# button.net
KiCad netlist of a schematic drawn in Altium Designer
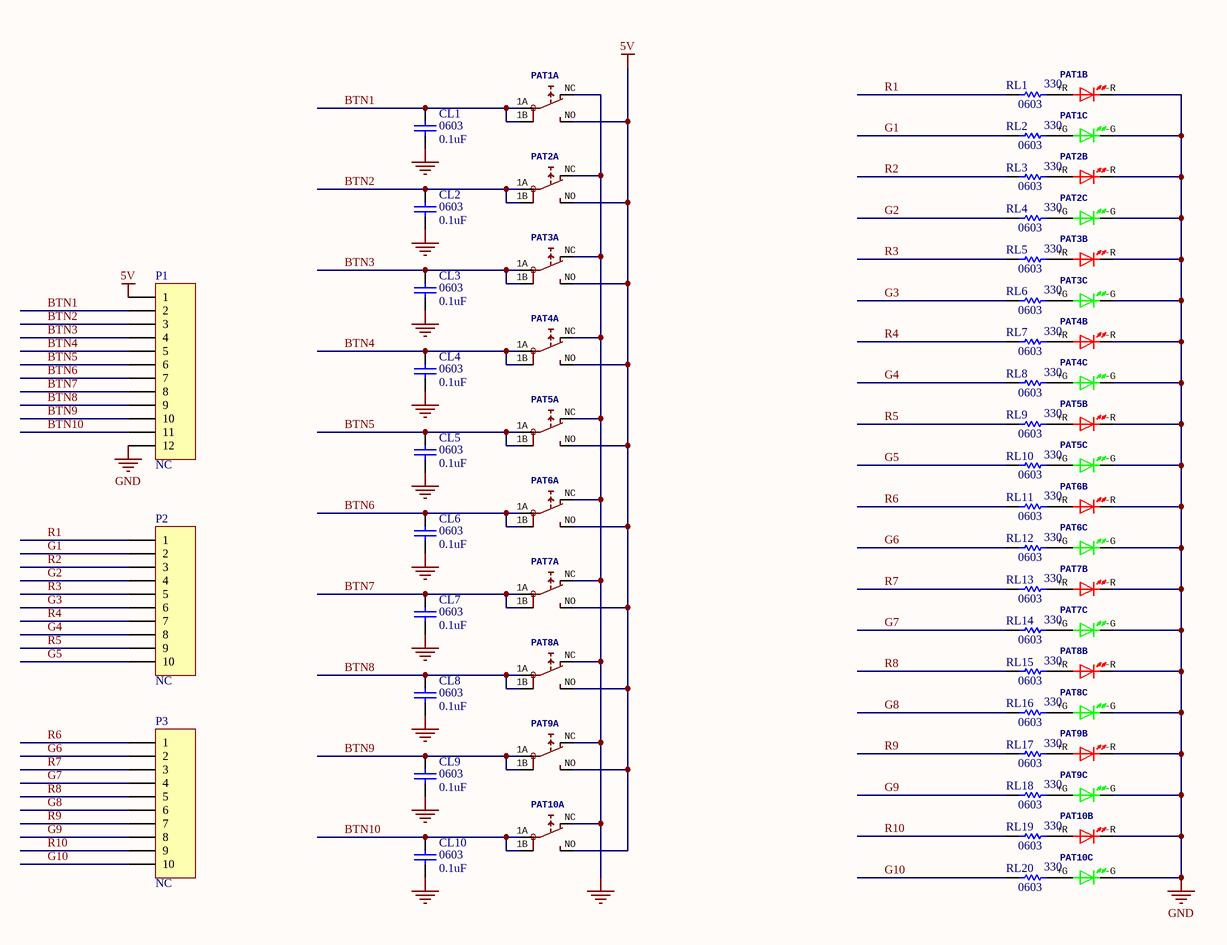
[diagram p0: button.SchDoc]

(export (version "E")
  (design (tool "Eeschema 10.0.6"))
  (components
    (comp (ref "CL1")
      (value "0603")
      (footprint "C0603")
      (description "CAP CER 0.1UF 50V X5R 0603")
      (fields (field (name "ALTIUM_VALUE") "0.1uF") (field (name "TOLERANCE") "10%"))
      (libsource (lib "Miscellaneous Devices") (part "Cap"))
    )
    (comp (ref "CL2")
      (value "0603")
      (footprint "C0603")
      (description "CAP CER 0.1UF 50V X5R 0603")
      (fields (field (name "ALTIUM_VALUE") "0.1uF") (field (name "TOLERANCE") "10%"))
      (libsource (lib "Miscellaneous Devices") (part "Cap"))
    )
    (comp (ref "CL3")
      (value "0603")
      (footprint "C0603")
      (description "CAP CER 0.1UF 50V X5R 0603")
      (fields (field (name "ALTIUM_VALUE") "0.1uF") (field (name "TOLERANCE") "10%"))
      (libsource (lib "Miscellaneous Devices") (part "Cap"))
    )
    (comp (ref "CL4")
      (value "0603")
      (footprint "C0603")
      (description "CAP CER 0.1UF 50V X5R 0603")
      (fields (field (name "ALTIUM_VALUE") "0.1uF") (field (name "TOLERANCE") "10%"))
      (libsource (lib "Miscellaneous Devices") (part "Cap"))
    )
    (comp (ref "CL5")
      (value "0603")
      (footprint "C0603")
      (description "CAP CER 0.1UF 50V X5R 0603")
      (fields (field (name "ALTIUM_VALUE") "0.1uF") (field (name "TOLERANCE") "10%"))
      (libsource (lib "Miscellaneous Devices") (part "Cap"))
    )
    (comp (ref "CL6")
      (value "0603")
      (footprint "C0603")
      (description "CAP CER 0.1UF 50V X5R 0603")
      (fields (field (name "ALTIUM_VALUE") "0.1uF") (field (name "TOLERANCE") "10%"))
      (libsource (lib "Miscellaneous Devices") (part "Cap"))
    )
    (comp (ref "CL7")
      (value "0603")
      (footprint "C0603")
      (description "CAP CER 0.1UF 50V X5R 0603")
      (fields (field (name "ALTIUM_VALUE") "0.1uF") (field (name "TOLERANCE") "10%"))
      (libsource (lib "Miscellaneous Devices") (part "Cap"))
    )
    (comp (ref "CL8")
      (value "0603")
      (footprint "C0603")
      (description "CAP CER 0.1UF 50V X5R 0603")
      (fields (field (name "ALTIUM_VALUE") "0.1uF") (field (name "TOLERANCE") "10%"))
      (libsource (lib "Miscellaneous Devices") (part "Cap"))
    )
    (comp (ref "CL9")
      (value "0603")
      (footprint "C0603")
      (description "CAP CER 0.1UF 50V X5R 0603")
      (fields (field (name "ALTIUM_VALUE") "0.1uF") (field (name "TOLERANCE") "10%"))
      (libsource (lib "Miscellaneous Devices") (part "Cap"))
    )
    (comp (ref "CL10")
      (value "0603")
      (footprint "C0603")
      (description "CAP CER 0.1UF 50V X5R 0603")
      (fields (field (name "ALTIUM_VALUE") "0.1uF") (field (name "TOLERANCE") "10%"))
      (libsource (lib "Miscellaneous Devices") (part "Cap"))
    )
    (comp (ref "P1")
      (value "NC")
      (footprint "12P HEADER")
      (description "Header, 12-Pin")
      (fields (field (name "PUBLISHER") "Altium Limited"))
      (libsource (lib "Miscellaneous Connectors") (part "Header 12"))
    )
    (comp (ref "P2")
      (value "NC")
      (footprint "10P HEADER")
      (description "Header, 10-Pin")
      (fields (field (name "PUBLISHER") "Altium Limited"))
      (libsource (lib "Miscellaneous Connectors") (part "Header 10"))
    )
    (comp (ref "P3")
      (value "NC")
      (footprint "10P HEADER")
      (description "Header, 10-Pin")
      (fields (field (name "PUBLISHER") "Altium Limited"))
      (libsource (lib "Miscellaneous Connectors") (part "Header 10"))
    )
    (comp (ref "PAT1")
      (value "55?-2LED01")
      (footprint "5501-2LED")
      (description "Pushbutton Switch SPDT Keyswitch, Illuminated Through Hole")
      (libsource (lib "Schlib") (part "5501MBLKREDGRN"))
    )
    (comp (ref "PAT2")
      (value "55?-2LED01")
      (footprint "5501-2LED")
      (description "Pushbutton Switch SPDT Keyswitch, Illuminated Through Hole")
      (libsource (lib "Schlib") (part "5501MBLKREDGRN"))
    )
    (comp (ref "PAT3")
      (value "55?-2LED01")
      (footprint "5501-2LED")
      (description "Pushbutton Switch SPDT Keyswitch, Illuminated Through Hole")
      (libsource (lib "Schlib") (part "5501MBLKREDGRN"))
    )
    (comp (ref "PAT4")
      (value "55?-2LED01")
      (footprint "5501-2LED")
      (description "Pushbutton Switch SPDT Keyswitch, Illuminated Through Hole")
      (libsource (lib "Schlib") (part "5501MBLKREDGRN"))
    )
    (comp (ref "PAT5")
      (value "55?-2LED01")
      (footprint "5501-2LED")
      (description "Pushbutton Switch SPDT Keyswitch, Illuminated Through Hole")
      (libsource (lib "Schlib") (part "5501MBLKREDGRN"))
    )
    (comp (ref "PAT6")
      (value "55?-2LED01")
      (footprint "5501-2LED")
      (description "Pushbutton Switch SPDT Keyswitch, Illuminated Through Hole")
      (libsource (lib "Schlib") (part "5501MBLKREDGRN"))
    )
    (comp (ref "PAT7")
      (value "55?-2LED01")
      (footprint "5501-2LED")
      (description "Pushbutton Switch SPDT Keyswitch, Illuminated Through Hole")
      (libsource (lib "Schlib") (part "5501MBLKREDGRN"))
    )
    (comp (ref "PAT8")
      (value "55?-2LED01")
      (footprint "5501-2LED")
      (description "Pushbutton Switch SPDT Keyswitch, Illuminated Through Hole")
      (libsource (lib "") (part "5501MBLKREDGRN_1"))
    )
    (comp (ref "PAT9")
      (value "55?-2LED01")
      (footprint "5501-2LED")
      (description "Pushbutton Switch SPDT Keyswitch, Illuminated Through Hole")
      (libsource (lib "Schlib") (part "5501MBLKREDGRN"))
    )
    (comp (ref "PAT10")
      (value "55?-2LED01")
      (footprint "5501-2LED")
      (description "Pushbutton Switch SPDT Keyswitch, Illuminated Through Hole")
      (libsource (lib "Schlib") (part "5501MBLKREDGRN"))
    )
    (comp (ref "RL1")
      (value "0603")
      (footprint "R0603")
      (description "RES SMD 330 OHM 1% 1/10W 0603")
      (fields (field (name "ALTIUM_VALUE") "330") (field (name "TOLERANCE") "1%"))
      (libsource (lib "Miscellaneous Devices") (part "Res1"))
    )
    (comp (ref "RL2")
      (value "0603")
      (footprint "R0603")
      (description "RES SMD 330 OHM 1% 1/10W 0603")
      (fields (field (name "ALTIUM_VALUE") "330") (field (name "TOLERANCE") "1%"))
      (libsource (lib "Miscellaneous Devices") (part "Res1"))
    )
    (comp (ref "RL3")
      (value "0603")
      (footprint "R0603")
      (description "RES SMD 330 OHM 1% 1/10W 0603")
      (fields (field (name "ALTIUM_VALUE") "330") (field (name "TOLERANCE") "1%"))
      (libsource (lib "Miscellaneous Devices") (part "Res1"))
    )
    (comp (ref "RL4")
      (value "0603")
      (footprint "R0603")
      (description "RES SMD 330 OHM 1% 1/10W 0603")
      (fields (field (name "ALTIUM_VALUE") "330") (field (name "TOLERANCE") "1%"))
      (libsource (lib "Miscellaneous Devices") (part "Res1"))
    )
    (comp (ref "RL5")
      (value "0603")
      (footprint "R0603")
      (description "RES SMD 330 OHM 1% 1/10W 0603")
      (fields (field (name "ALTIUM_VALUE") "330") (field (name "TOLERANCE") "1%"))
      (libsource (lib "Miscellaneous Devices") (part "Res1"))
    )
    (comp (ref "RL6")
      (value "0603")
      (footprint "R0603")
      (description "RES SMD 330 OHM 1% 1/10W 0603")
      (fields (field (name "ALTIUM_VALUE") "330") (field (name "TOLERANCE") "1%"))
      (libsource (lib "Miscellaneous Devices") (part "Res1"))
    )
    (comp (ref "RL7")
      (value "0603")
      (footprint "R0603")
      (description "RES SMD 330 OHM 1% 1/10W 0603")
      (fields (field (name "ALTIUM_VALUE") "330") (field (name "TOLERANCE") "1%"))
      (libsource (lib "Miscellaneous Devices") (part "Res1"))
    )
    (comp (ref "RL8")
      (value "0603")
      (footprint "R0603")
      (description "RES SMD 330 OHM 1% 1/10W 0603")
      (fields (field (name "ALTIUM_VALUE") "330") (field (name "TOLERANCE") "1%"))
      (libsource (lib "Miscellaneous Devices") (part "Res1"))
    )
    (comp (ref "RL9")
      (value "0603")
      (footprint "R0603")
      (description "RES SMD 330 OHM 1% 1/10W 0603")
      (fields (field (name "ALTIUM_VALUE") "330") (field (name "TOLERANCE") "1%"))
      (libsource (lib "Miscellaneous Devices") (part "Res1"))
    )
    (comp (ref "RL10")
      (value "0603")
      (footprint "R0603")
      (description "RES SMD 330 OHM 1% 1/10W 0603")
      (fields (field (name "ALTIUM_VALUE") "330") (field (name "TOLERANCE") "1%"))
      (libsource (lib "Miscellaneous Devices") (part "Res1"))
    )
    (comp (ref "RL11")
      (value "0603")
      (footprint "R0603")
      (description "RES SMD 330 OHM 1% 1/10W 0603")
      (fields (field (name "ALTIUM_VALUE") "330") (field (name "TOLERANCE") "1%"))
      (libsource (lib "Miscellaneous Devices") (part "Res1"))
    )
    (comp (ref "RL12")
      (value "0603")
      (footprint "R0603")
      (description "RES SMD 330 OHM 1% 1/10W 0603")
      (fields (field (name "ALTIUM_VALUE") "330") (field (name "TOLERANCE") "1%"))
      (libsource (lib "Miscellaneous Devices") (part "Res1"))
    )
    (comp (ref "RL13")
      (value "0603")
      (footprint "R0603")
      (description "RES SMD 330 OHM 1% 1/10W 0603")
      (fields (field (name "ALTIUM_VALUE") "330") (field (name "TOLERANCE") "1%"))
      (libsource (lib "Miscellaneous Devices") (part "Res1"))
    )
    (comp (ref "RL14")
      (value "0603")
      (footprint "R0603")
      (description "RES SMD 330 OHM 1% 1/10W 0603")
      (fields (field (name "ALTIUM_VALUE") "330") (field (name "TOLERANCE") "1%"))
      (libsource (lib "Miscellaneous Devices") (part "Res1"))
    )
    (comp (ref "RL15")
      (value "0603")
      (footprint "R0603")
      (description "RES SMD 330 OHM 1% 1/10W 0603")
      (fields (field (name "ALTIUM_VALUE") "330") (field (name "TOLERANCE") "1%"))
      (libsource (lib "Miscellaneous Devices") (part "Res1"))
    )
    (comp (ref "RL16")
      (value "0603")
      (footprint "R0603")
      (description "RES SMD 330 OHM 1% 1/10W 0603")
      (fields (field (name "ALTIUM_VALUE") "330") (field (name "TOLERANCE") "1%"))
      (libsource (lib "Miscellaneous Devices") (part "Res1"))
    )
    (comp (ref "RL17")
      (value "0603")
      (footprint "R0603")
      (description "RES SMD 330 OHM 1% 1/10W 0603")
      (fields (field (name "ALTIUM_VALUE") "330") (field (name "TOLERANCE") "1%"))
      (libsource (lib "Miscellaneous Devices") (part "Res1"))
    )
    (comp (ref "RL18")
      (value "0603")
      (footprint "R0603")
      (description "RES SMD 330 OHM 1% 1/10W 0603")
      (fields (field (name "ALTIUM_VALUE") "330") (field (name "TOLERANCE") "1%"))
      (libsource (lib "Miscellaneous Devices") (part "Res1"))
    )
    (comp (ref "RL19")
      (value "0603")
      (footprint "R0603")
      (description "RES SMD 330 OHM 1% 1/10W 0603")
      (fields (field (name "ALTIUM_VALUE") "330") (field (name "TOLERANCE") "1%"))
      (libsource (lib "Miscellaneous Devices") (part "Res1"))
    )
    (comp (ref "RL20")
      (value "0603")
      (footprint "R0603")
      (description "RES SMD 330 OHM 1% 1/10W 0603")
      (fields (field (name "ALTIUM_VALUE") "330") (field (name "TOLERANCE") "1%"))
      (libsource (lib "Miscellaneous Devices") (part "Res1"))
    )
  )
  (nets
    (net (code "1") (name "/BTN1") (class "Default")
      (node (ref "CL1") (pin "2") (pinfunction "2_2") (pintype "passive"))
      (node (ref "P1") (pin "2") (pinfunction "2_2") (pintype "passive"))
      (node (ref "PAT1") (pin "1A") (pinfunction "1A_1A") (pintype "passive"))
      (node (ref "PAT1") (pin "1B") (pinfunction "1B_1B") (pintype "passive"))
    )
    (net (code "2") (name "/BTN2") (class "Default")
      (node (ref "CL2") (pin "2") (pinfunction "2_2") (pintype "passive"))
      (node (ref "P1") (pin "3") (pinfunction "3_3") (pintype "passive"))
      (node (ref "PAT2") (pin "1A") (pinfunction "1A_1A") (pintype "passive"))
      (node (ref "PAT2") (pin "1B") (pinfunction "1B_1B") (pintype "passive"))
    )
    (net (code "3") (name "/BTN3") (class "Default")
      (node (ref "CL3") (pin "2") (pinfunction "2_2") (pintype "passive"))
      (node (ref "P1") (pin "4") (pinfunction "4_4") (pintype "passive"))
      (node (ref "PAT3") (pin "1A") (pinfunction "1A_1A") (pintype "passive"))
      (node (ref "PAT3") (pin "1B") (pinfunction "1B_1B") (pintype "passive"))
    )
    (net (code "4") (name "/BTN4") (class "Default")
      (node (ref "CL4") (pin "2") (pinfunction "2_2") (pintype "passive"))
      (node (ref "P1") (pin "5") (pinfunction "5_5") (pintype "passive"))
      (node (ref "PAT4") (pin "1A") (pinfunction "1A_1A") (pintype "passive"))
      (node (ref "PAT4") (pin "1B") (pinfunction "1B_1B") (pintype "passive"))
    )
    (net (code "5") (name "/BTN5") (class "Default")
      (node (ref "CL5") (pin "2") (pinfunction "2_2") (pintype "passive"))
      (node (ref "P1") (pin "6") (pinfunction "6_6") (pintype "passive"))
      (node (ref "PAT5") (pin "1A") (pinfunction "1A_1A") (pintype "passive"))
      (node (ref "PAT5") (pin "1B") (pinfunction "1B_1B") (pintype "passive"))
    )
    (net (code "6") (name "/BTN6") (class "Default")
      (node (ref "CL6") (pin "2") (pinfunction "2_2") (pintype "passive"))
      (node (ref "P1") (pin "7") (pinfunction "7_7") (pintype "passive"))
      (node (ref "PAT6") (pin "1A") (pinfunction "1A_1A") (pintype "passive"))
      (node (ref "PAT6") (pin "1B") (pinfunction "1B_1B") (pintype "passive"))
    )
    (net (code "7") (name "/BTN7") (class "Default")
      (node (ref "CL7") (pin "2") (pinfunction "2_2") (pintype "passive"))
      (node (ref "P1") (pin "8") (pinfunction "8_8") (pintype "passive"))
      (node (ref "PAT7") (pin "1A") (pinfunction "1A_1A") (pintype "passive"))
      (node (ref "PAT7") (pin "1B") (pinfunction "1B_1B") (pintype "passive"))
    )
    (net (code "8") (name "/BTN8") (class "Default")
      (node (ref "CL8") (pin "2") (pinfunction "2_2") (pintype "passive"))
      (node (ref "P1") (pin "9") (pinfunction "9_9") (pintype "passive"))
      (node (ref "PAT8") (pin "1A") (pinfunction "1A_1A") (pintype "passive"))
      (node (ref "PAT8") (pin "1B") (pinfunction "1B_1B") (pintype "passive"))
    )
    (net (code "9") (name "/BTN9") (class "Default")
      (node (ref "CL9") (pin "2") (pinfunction "2_2") (pintype "passive"))
      (node (ref "P1") (pin "10") (pinfunction "10_10") (pintype "passive"))
      (node (ref "PAT9") (pin "1A") (pinfunction "1A_1A") (pintype "passive"))
      (node (ref "PAT9") (pin "1B") (pinfunction "1B_1B") (pintype "passive"))
    )
    (net (code "10") (name "/BTN10") (class "Default")
      (node (ref "CL10") (pin "2") (pinfunction "2_2") (pintype "passive"))
      (node (ref "P1") (pin "11") (pinfunction "11_11") (pintype "passive"))
      (node (ref "PAT10") (pin "1A") (pinfunction "1A_1A") (pintype "passive"))
      (node (ref "PAT10") (pin "1B") (pinfunction "1B_1B") (pintype "passive"))
    )
    (net (code "11") (name "/G1") (class "Default")
      (node (ref "P2") (pin "2") (pinfunction "2_2") (pintype "passive"))
      (node (ref "RL2") (pin "1") (pinfunction "1_1") (pintype "passive"))
    )
    (net (code "12") (name "/G2") (class "Default")
      (node (ref "P2") (pin "4") (pinfunction "4_4") (pintype "passive"))
      (node (ref "RL4") (pin "1") (pinfunction "1_1") (pintype "passive"))
    )
    (net (code "13") (name "/G3") (class "Default")
      (node (ref "P2") (pin "6") (pinfunction "6_6") (pintype "passive"))
      (node (ref "RL6") (pin "1") (pinfunction "1_1") (pintype "passive"))
    )
    (net (code "14") (name "/G4") (class "Default")
      (node (ref "P2") (pin "8") (pinfunction "8_8") (pintype "passive"))
      (node (ref "RL8") (pin "1") (pinfunction "1_1") (pintype "passive"))
    )
    (net (code "15") (name "/G5") (class "Default")
      (node (ref "P2") (pin "10") (pinfunction "10_10") (pintype "passive"))
      (node (ref "RL10") (pin "1") (pinfunction "1_1") (pintype "passive"))
    )
    (net (code "16") (name "/G6") (class "Default")
      (node (ref "P3") (pin "2") (pinfunction "2_2") (pintype "passive"))
      (node (ref "RL12") (pin "1") (pinfunction "1_1") (pintype "passive"))
    )
    (net (code "17") (name "/G7") (class "Default")
      (node (ref "P3") (pin "4") (pinfunction "4_4") (pintype "passive"))
      (node (ref "RL14") (pin "1") (pinfunction "1_1") (pintype "passive"))
    )
    (net (code "18") (name "/G8") (class "Default")
      (node (ref "P3") (pin "6") (pinfunction "6_6") (pintype "passive"))
      (node (ref "RL16") (pin "1") (pinfunction "1_1") (pintype "passive"))
    )
    (net (code "19") (name "/G9") (class "Default")
      (node (ref "P3") (pin "8") (pinfunction "8_8") (pintype "passive"))
      (node (ref "RL18") (pin "1") (pinfunction "1_1") (pintype "passive"))
    )
    (net (code "20") (name "/G10") (class "Default")
      (node (ref "P3") (pin "10") (pinfunction "10_10") (pintype "passive"))
      (node (ref "RL20") (pin "1") (pinfunction "1_1") (pintype "passive"))
    )
    (net (code "21") (name "/R1") (class "Default")
      (node (ref "P2") (pin "1") (pinfunction "1_1") (pintype "passive"))
      (node (ref "RL1") (pin "1") (pinfunction "1_1") (pintype "passive"))
    )
    (net (code "22") (name "/R2") (class "Default")
      (node (ref "P2") (pin "3") (pinfunction "3_3") (pintype "passive"))
      (node (ref "RL3") (pin "1") (pinfunction "1_1") (pintype "passive"))
    )
    (net (code "23") (name "/R3") (class "Default")
      (node (ref "P2") (pin "5") (pinfunction "5_5") (pintype "passive"))
      (node (ref "RL5") (pin "1") (pinfunction "1_1") (pintype "passive"))
    )
    (net (code "24") (name "/R4") (class "Default")
      (node (ref "P2") (pin "7") (pinfunction "7_7") (pintype "passive"))
      (node (ref "RL7") (pin "1") (pinfunction "1_1") (pintype "passive"))
    )
    (net (code "25") (name "/R5") (class "Default")
      (node (ref "P2") (pin "9") (pinfunction "9_9") (pintype "passive"))
      (node (ref "RL9") (pin "1") (pinfunction "1_1") (pintype "passive"))
    )
    (net (code "26") (name "/R6") (class "Default")
      (node (ref "P3") (pin "1") (pinfunction "1_1") (pintype "passive"))
      (node (ref "RL11") (pin "1") (pinfunction "1_1") (pintype "passive"))
    )
    (net (code "27") (name "/R7") (class "Default")
      (node (ref "P3") (pin "3") (pinfunction "3_3") (pintype "passive"))
      (node (ref "RL13") (pin "1") (pinfunction "1_1") (pintype "passive"))
    )
    (net (code "28") (name "/R8") (class "Default")
      (node (ref "P3") (pin "5") (pinfunction "5_5") (pintype "passive"))
      (node (ref "RL15") (pin "1") (pinfunction "1_1") (pintype "passive"))
    )
    (net (code "29") (name "/R9") (class "Default")
      (node (ref "P3") (pin "7") (pinfunction "7_7") (pintype "passive"))
      (node (ref "RL17") (pin "1") (pinfunction "1_1") (pintype "passive"))
    )
    (net (code "30") (name "/R10") (class "Default")
      (node (ref "P3") (pin "9") (pinfunction "9_9") (pintype "passive"))
      (node (ref "RL19") (pin "1") (pinfunction "1_1") (pintype "passive"))
    )
    (net (code "31") (name "5V") (class "Default")
      (node (ref "P1") (pin "1") (pinfunction "1_1") (pintype "passive"))
      (node (ref "PAT1") (pin "NO") (pinfunction "NO_NO") (pintype "passive"))
      (node (ref "PAT10") (pin "NO") (pinfunction "NO_NO") (pintype "passive"))
      (node (ref "PAT2") (pin "NO") (pinfunction "NO_NO") (pintype "passive"))
      (node (ref "PAT3") (pin "NO") (pinfunction "NO_NO") (pintype "passive"))
      (node (ref "PAT4") (pin "NO") (pinfunction "NO_NO") (pintype "passive"))
      (node (ref "PAT5") (pin "NO") (pinfunction "NO_NO") (pintype "passive"))
      (node (ref "PAT6") (pin "NO") (pinfunction "NO_NO") (pintype "passive"))
      (node (ref "PAT7") (pin "NO") (pinfunction "NO_NO") (pintype "passive"))
      (node (ref "PAT8") (pin "NO") (pinfunction "NO_NO") (pintype "passive"))
      (node (ref "PAT9") (pin "NO") (pinfunction "NO_NO") (pintype "passive"))
    )
    (net (code "32") (name "GND") (class "Default")
      (node (ref "CL1") (pin "1") (pinfunction "1_1") (pintype "passive"))
      (node (ref "CL10") (pin "1") (pinfunction "1_1") (pintype "passive"))
      (node (ref "CL2") (pin "1") (pinfunction "1_1") (pintype "passive"))
      (node (ref "CL3") (pin "1") (pinfunction "1_1") (pintype "passive"))
      (node (ref "CL4") (pin "1") (pinfunction "1_1") (pintype "passive"))
      (node (ref "CL5") (pin "1") (pinfunction "1_1") (pintype "passive"))
      (node (ref "CL6") (pin "1") (pinfunction "1_1") (pintype "passive"))
      (node (ref "CL7") (pin "1") (pinfunction "1_1") (pintype "passive"))
      (node (ref "CL8") (pin "1") (pinfunction "1_1") (pintype "passive"))
      (node (ref "CL9") (pin "1") (pinfunction "1_1") (pintype "passive"))
      (node (ref "P1") (pin "12") (pinfunction "12_12") (pintype "passive"))
      (node (ref "PAT1") (pin "-G") (pinfunction "K_-G") (pintype "passive"))
      (node (ref "PAT1") (pin "-R") (pinfunction "K_-R") (pintype "passive"))
      (node (ref "PAT1") (pin "NC") (pinfunction "NC_NC") (pintype "passive"))
      (node (ref "PAT10") (pin "-G") (pinfunction "K_-G") (pintype "passive"))
      (node (ref "PAT10") (pin "-R") (pinfunction "K_-R") (pintype "passive"))
      (node (ref "PAT10") (pin "NC") (pinfunction "NC_NC") (pintype "passive"))
      (node (ref "PAT2") (pin "-G") (pinfunction "K_-G") (pintype "passive"))
      (node (ref "PAT2") (pin "-R") (pinfunction "K_-R") (pintype "passive"))
      (node (ref "PAT2") (pin "NC") (pinfunction "NC_NC") (pintype "passive"))
      (node (ref "PAT3") (pin "-G") (pinfunction "K_-G") (pintype "passive"))
      (node (ref "PAT3") (pin "-R") (pinfunction "K_-R") (pintype "passive"))
      (node (ref "PAT3") (pin "NC") (pinfunction "NC_NC") (pintype "passive"))
      (node (ref "PAT4") (pin "-G") (pinfunction "K_-G") (pintype "passive"))
      (node (ref "PAT4") (pin "-R") (pinfunction "K_-R") (pintype "passive"))
      (node (ref "PAT4") (pin "NC") (pinfunction "NC_NC") (pintype "passive"))
      (node (ref "PAT5") (pin "-G") (pinfunction "K_-G") (pintype "passive"))
      (node (ref "PAT5") (pin "-R") (pinfunction "K_-R") (pintype "passive"))
      (node (ref "PAT5") (pin "NC") (pinfunction "NC_NC") (pintype "passive"))
      (node (ref "PAT6") (pin "-G") (pinfunction "K_-G") (pintype "passive"))
      (node (ref "PAT6") (pin "-R") (pinfunction "K_-R") (pintype "passive"))
      (node (ref "PAT6") (pin "NC") (pinfunction "NC_NC") (pintype "passive"))
      (node (ref "PAT7") (pin "-G") (pinfunction "K_-G") (pintype "passive"))
      (node (ref "PAT7") (pin "-R") (pinfunction "K_-R") (pintype "passive"))
      (node (ref "PAT7") (pin "NC") (pinfunction "NC_NC") (pintype "passive"))
      (node (ref "PAT8") (pin "-G") (pinfunction "K_-G") (pintype "passive"))
      (node (ref "PAT8") (pin "-R") (pinfunction "K_-R") (pintype "passive"))
      (node (ref "PAT8") (pin "NC") (pinfunction "NC_NC") (pintype "passive"))
      (node (ref "PAT9") (pin "-G") (pinfunction "K_-G") (pintype "passive"))
      (node (ref "PAT9") (pin "-R") (pinfunction "K_-R") (pintype "passive"))
      (node (ref "PAT9") (pin "NC") (pinfunction "NC_NC") (pintype "passive"))
    )
    (net (code "33") (name "Net-(PAT1B-A)") (class "Default")
      (node (ref "PAT1") (pin "+R") (pinfunction "A_+R") (pintype "passive"))
      (node (ref "RL1") (pin "2") (pinfunction "2_2") (pintype "passive"))
    )
    (net (code "34") (name "Net-(PAT1C-A)") (class "Default")
      (node (ref "PAT1") (pin "+G") (pinfunction "A_+G") (pintype "passive"))
      (node (ref "RL2") (pin "2") (pinfunction "2_2") (pintype "passive"))
    )
    (net (code "35") (name "Net-(PAT2B-A)") (class "Default")
      (node (ref "PAT2") (pin "+R") (pinfunction "A_+R") (pintype "passive"))
      (node (ref "RL3") (pin "2") (pinfunction "2_2") (pintype "passive"))
    )
    (net (code "36") (name "Net-(PAT2C-A)") (class "Default")
      (node (ref "PAT2") (pin "+G") (pinfunction "A_+G") (pintype "passive"))
      (node (ref "RL4") (pin "2") (pinfunction "2_2") (pintype "passive"))
    )
    (net (code "37") (name "Net-(PAT3B-A)") (class "Default")
      (node (ref "PAT3") (pin "+R") (pinfunction "A_+R") (pintype "passive"))
      (node (ref "RL5") (pin "2") (pinfunction "2_2") (pintype "passive"))
    )
    (net (code "38") (name "Net-(PAT3C-A)") (class "Default")
      (node (ref "PAT3") (pin "+G") (pinfunction "A_+G") (pintype "passive"))
      (node (ref "RL6") (pin "2") (pinfunction "2_2") (pintype "passive"))
    )
    (net (code "39") (name "Net-(PAT4B-A)") (class "Default")
      (node (ref "PAT4") (pin "+R") (pinfunction "A_+R") (pintype "passive"))
      (node (ref "RL7") (pin "2") (pinfunction "2_2") (pintype "passive"))
    )
    (net (code "40") (name "Net-(PAT4C-A)") (class "Default")
      (node (ref "PAT4") (pin "+G") (pinfunction "A_+G") (pintype "passive"))
      (node (ref "RL8") (pin "2") (pinfunction "2_2") (pintype "passive"))
    )
    (net (code "41") (name "Net-(PAT5B-A)") (class "Default")
      (node (ref "PAT5") (pin "+R") (pinfunction "A_+R") (pintype "passive"))
      (node (ref "RL9") (pin "2") (pinfunction "2_2") (pintype "passive"))
    )
    (net (code "42") (name "Net-(PAT5C-A)") (class "Default")
      (node (ref "PAT5") (pin "+G") (pinfunction "A_+G") (pintype "passive"))
      (node (ref "RL10") (pin "2") (pinfunction "2_2") (pintype "passive"))
    )
    (net (code "43") (name "Net-(PAT6B-A)") (class "Default")
      (node (ref "PAT6") (pin "+R") (pinfunction "A_+R") (pintype "passive"))
      (node (ref "RL11") (pin "2") (pinfunction "2_2") (pintype "passive"))
    )
    (net (code "44") (name "Net-(PAT6C-A)") (class "Default")
      (node (ref "PAT6") (pin "+G") (pinfunction "A_+G") (pintype "passive"))
      (node (ref "RL12") (pin "2") (pinfunction "2_2") (pintype "passive"))
    )
    (net (code "45") (name "Net-(PAT7B-A)") (class "Default")
      (node (ref "PAT7") (pin "+R") (pinfunction "A_+R") (pintype "passive"))
      (node (ref "RL13") (pin "2") (pinfunction "2_2") (pintype "passive"))
    )
    (net (code "46") (name "Net-(PAT7C-A)") (class "Default")
      (node (ref "PAT7") (pin "+G") (pinfunction "A_+G") (pintype "passive"))
      (node (ref "RL14") (pin "2") (pinfunction "2_2") (pintype "passive"))
    )
    (net (code "47") (name "Net-(PAT8B-A)") (class "Default")
      (node (ref "PAT8") (pin "+R") (pinfunction "A_+R") (pintype "passive"))
      (node (ref "RL15") (pin "2") (pinfunction "2_2") (pintype "passive"))
    )
    (net (code "48") (name "Net-(PAT8C-A)") (class "Default")
      (node (ref "PAT8") (pin "+G") (pinfunction "A_+G") (pintype "passive"))
      (node (ref "RL16") (pin "2") (pinfunction "2_2") (pintype "passive"))
    )
    (net (code "49") (name "Net-(PAT9B-A)") (class "Default")
      (node (ref "PAT9") (pin "+R") (pinfunction "A_+R") (pintype "passive"))
      (node (ref "RL17") (pin "2") (pinfunction "2_2") (pintype "passive"))
    )
    (net (code "50") (name "Net-(PAT9C-A)") (class "Default")
      (node (ref "PAT9") (pin "+G") (pinfunction "A_+G") (pintype "passive"))
      (node (ref "RL18") (pin "2") (pinfunction "2_2") (pintype "passive"))
    )
    (net (code "51") (name "Net-(PAT10B-A)") (class "Default")
      (node (ref "PAT10") (pin "+R") (pinfunction "A_+R") (pintype "passive"))
      (node (ref "RL19") (pin "2") (pinfunction "2_2") (pintype "passive"))
    )
    (net (code "52") (name "Net-(PAT10C-A)") (class "Default")
      (node (ref "PAT10") (pin "+G") (pinfunction "A_+G") (pintype "passive"))
      (node (ref "RL20") (pin "2") (pinfunction "2_2") (pintype "passive"))
    )
  )
)
